# RADIO.net
KiCad netlist of a schematic drawn in Altium Designer
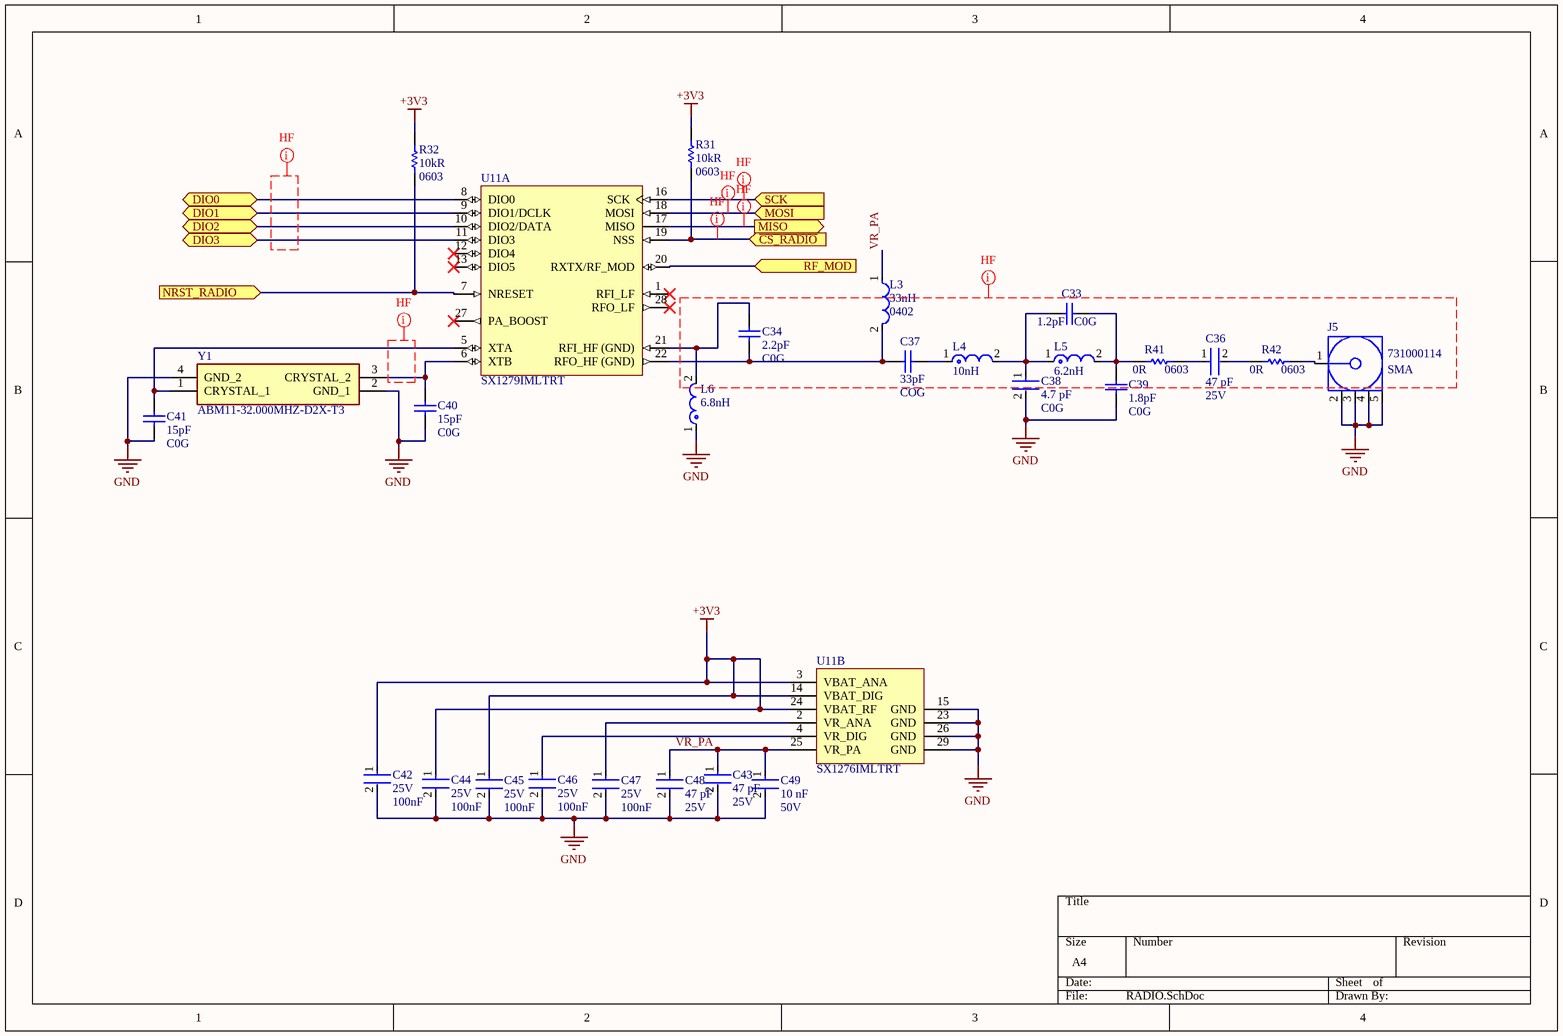
[diagram p0: RADIO.SchDoc]

(export (version "E")
  (design (tool "Eeschema 10.0.6"))
  (components
    (comp (ref "C33")
      (value "06032U1R2BAT2A")
      (footprint "CAPC1508X91X25LL25T13")
      (fields
        (field (name "MANUFACTURER") "AVX Interconnect / Elco")
        (field (name "CAPACITANCE") "1.2pF")
        (field (name "DIELECTRIC") "C0G")
        (field (name "VOLTAGE") "200V")
        (field (name "TOLERANCE") "2%")
      )
      (libsource (lib "Altium Content Vault") (part "CAP"))
    )
    (comp (ref "C34")
      (value "04023A2R2CAT2A")
      (footprint "CAPC1005X56X25ML10T15")
      (fields
        (field (name "MANUFACTURER") "AVX Interconnect / Elco")
        (field (name "CAPACITANCE") "2.2pF")
        (field (name "DIELECTRIC") "C0G")
      )
      (libsource (lib "Altium Content Vault") (part "CAP"))
    )
    (comp (ref "C36")
      (value "C0603C470J3GACTU")
      (footprint "FP-C0603C-CF-MFG")
      (description "CAP CER 47PF 25V 5% NP0 0603")
      (fields
        (field (name "CAPACITANCE") "47 pF")
        (field (name "OCTOPART") "https://octopart.com/c0603c470j3gactu-kemet-8375742")
        (field (name "MANUFACTURER") "KEMET")
        (field (name "VOLTAGE RATING (DC)") "25V")
      )
      (libsource (lib "Altium Content Vault") (part "b4654b650e69147ec39a6b967a45e02"))
    )
    (comp (ref "C37")
      (value "CC0603JRNPO9BN330")
      (footprint "CAPC1608X90X40LL10T20")
      (description "Chip Capacitor, 33 pF, +/- 5%, 50 V, -55 to 125 degC, 0603 (1608 Metric), RoHS, Tape and Reel")
      (fields
        (field (name "MANUFACTURER") "Yageo")
        (field (name "TOLERANCE") "±5%")
        (field (name "CAPACITANCE") "33pF")
        (field (name "TEMPERATURE COEFFICIENT") "COG")
      )
      (libsource (lib "Altium Content Vault") (part "CAP-NP-2"))
    )
    (comp (ref "C38")
      (value "C0603C479C5GACTU")
      (footprint "FP-C0603C-CF-MFG")
      (description "CAP CER 4.7PF 50V NP0 0603")
      (fields
        (field (name "OCTOPART") "https://octopart.com/c0603c479c5gactu-kemet-3648287")
        (field (name "TOLERANCE") "0.25 pF")
        (field (name "CAPACITANCE") "4.7 pF")
        (field (name "TEMPERATURE CHARACTERISTIC") "C0G")
      )
      (libsource (lib "Altium Content Vault") (part "b4654b650e69147ec39a6b967a45e02"))
    )
    (comp (ref "C39")
      (value "06032U1R8BAT2A")
      (footprint "CAPC1508X91X25NL25T13")
      (fields
        (field (name "MANUFACTURER") "AVX Interconnect / Elco")
        (field (name "CAPACITANCE") "1.8pF")
        (field (name "DIELECTRIC") "C0G")
        (field (name "VOLTAGE") "200V")
      )
      (libsource (lib "Altium Content Vault") (part "CAP"))
    )
    (comp (ref "C40")
      (value "VJ0603D150JXPAJ")
      (footprint "CAPC1608X92X38ML15T08")
      (fields
        (field (name "MANUFACTURER") "Vitramon")
        (field (name "TOLERANCE") "5%")
        (field (name "CAPACITANCE") "15pF")
        (field (name "DIELECTRIC") "C0G")
        (field (name "VOLTAGE") "250V")
      )
      (libsource (lib "Altium Content Vault") (part "CAP"))
    )
    (comp (ref "C41")
      (value "VJ0603D150JXPAJ")
      (footprint "CAPC1608X92X38ML15T08")
      (fields
        (field (name "MANUFACTURER") "Vitramon")
        (field (name "TOLERANCE") "5%")
        (field (name "CAPACITANCE") "15pF")
        (field (name "DIELECTRIC") "C0G")
        (field (name "VOLTAGE") "250V")
      )
      (libsource (lib "Altium Content Vault") (part "CAP"))
    )
    (comp (ref "C42")
      (value "CGA3E2X7R1E104K080AA")
      (footprint "FP-CGA3E-0_3-0_1-MFG")
      (description "Cap Ceramic 100nF 25V X7R 10% Pad SMD 0603 +125°C Automotive T/R")
      (fields
        (field (name "VOLTAGE RATING (DC)") "25V")
        (field (name "CAPACITANCE") "100nF")
        (field (name "TOLERANCE") "10%")
        (field (name "MANUFACTURER") "TDK")
      )
      (libsource (lib "Altium Content Vault") (part "b4654b650e69147ec39a6b967a45e02"))
    )
    (comp (ref "C43")
      (value "C0603C470J3GACTU")
      (footprint "FP-C0603C-CF-MFG")
      (description "CAP CER 47PF 25V 5% NP0 0603")
      (fields
        (field (name "CAPACITANCE") "47 pF")
        (field (name "OCTOPART") "https://octopart.com/c0603c470j3gactu-kemet-8375742")
        (field (name "MANUFACTURER") "KEMET")
        (field (name "VOLTAGE RATING (DC)") "25V")
      )
      (libsource (lib "Altium Content Vault") (part "b4654b650e69147ec39a6b967a45e02"))
    )
    (comp (ref "C44")
      (value "CGA3E2X7R1E104K080AA")
      (footprint "FP-CGA3E-0_3-0_1-MFG")
      (description "Cap Ceramic 100nF 25V X7R 10% Pad SMD 0603 +125°C Automotive T/R")
      (fields
        (field (name "VOLTAGE RATING (DC)") "25V")
        (field (name "CAPACITANCE") "100nF")
        (field (name "TOLERANCE") "10%")
        (field (name "MANUFACTURER") "TDK")
      )
      (libsource (lib "Altium Content Vault") (part "b4654b650e69147ec39a6b967a45e02"))
    )
    (comp (ref "C45")
      (value "CGA3E2X7R1E104K080AA")
      (footprint "FP-CGA3E-0_3-0_1-MFG")
      (description "Cap Ceramic 100nF 25V X7R 10% Pad SMD 0603 +125°C Automotive T/R")
      (fields
        (field (name "VOLTAGE RATING (DC)") "25V")
        (field (name "CAPACITANCE") "100nF")
        (field (name "TOLERANCE") "10%")
        (field (name "MANUFACTURER") "TDK")
      )
      (libsource (lib "Altium Content Vault") (part "b4654b650e69147ec39a6b967a45e02"))
    )
    (comp (ref "C46")
      (value "CGA3E2X7R1E104K080AA")
      (footprint "FP-CGA3E-0_3-0_1-MFG")
      (description "Cap Ceramic 100nF 25V X7R 10% Pad SMD 0603 +125°C Automotive T/R")
      (fields
        (field (name "VOLTAGE RATING (DC)") "25V")
        (field (name "CAPACITANCE") "100nF")
        (field (name "TOLERANCE") "10%")
        (field (name "MANUFACTURER") "TDK")
      )
      (libsource (lib "Altium Content Vault") (part "b4654b650e69147ec39a6b967a45e02"))
    )
    (comp (ref "C47")
      (value "CGA3E2X7R1E104K080AA")
      (footprint "FP-CGA3E-0_3-0_1-MFG")
      (description "Cap Ceramic 100nF 25V X7R 10% Pad SMD 0603 +125°C Automotive T/R")
      (fields
        (field (name "VOLTAGE RATING (DC)") "25V")
        (field (name "CAPACITANCE") "100nF")
        (field (name "TOLERANCE") "10%")
        (field (name "MANUFACTURER") "TDK")
      )
      (libsource (lib "Altium Content Vault") (part "b4654b650e69147ec39a6b967a45e02"))
    )
    (comp (ref "C48")
      (value "C0603C470J3GACTU")
      (footprint "FP-C0603C-CF-MFG")
      (description "CAP CER 47PF 25V 5% NP0 0603")
      (fields
        (field (name "CAPACITANCE") "47 pF")
        (field (name "OCTOPART") "https://octopart.com/c0603c470j3gactu-kemet-8375742")
        (field (name "MANUFACTURER") "KEMET")
        (field (name "VOLTAGE RATING (DC)") "25V")
      )
      (libsource (lib "Altium Content Vault") (part "b4654b650e69147ec39a6b967a45e02"))
    )
    (comp (ref "C49")
      (value "CC0603KRX7R9BB103")
      (footprint "FP-CC0603-DA-MFG")
      (description "CAP CER 10000PF 50V X7R 0603")
      (fields
        (field (name "TOLERANCE") "0.1")
        (field (name "MANUFACTURER") "YAGEO")
        (field (name "CAPACITANCE") "10 nF")
        (field (name "VOLTAGE RATING (DC)") "50V")
      )
      (libsource (lib "Altium Content Vault") (part "11868f565c42a9108669ba33697ecf6"))
    )
    (comp (ref "J5")
      (value "731000114")
      (footprint "MOLX-731000114_V")
      (description "SMA Right-Angle PCB Jack Receptacle, Brass Body, Gold Plated, 50 Ohm, 5-Pin THD, RoHS, Tray")
      (fields
        (field (name "MANUFACTURER") "Molex")
        (field (name "MANUFACTURER PART NUMBER") "73100-0114")
        (field (name "CASE/PACKAGE") "SMA")
      )
      (libsource (lib "Altium Content Vault") (part "CN-S-4F-RF5"))
    )
    (comp (ref "L3")
      (value "LQW15AN33NJ00D")
      (footprint "FP-LQW15AN_00-W0_5-0_1-MFG")
      (description "Wire Wound RF Inductor 33nH ±5% 260mA 0.63Ω 0402 (1005)")
      (fields
        (field (name "TOLERANCE") "5%")
        (field (name "INDUCTANCE") "33nH")
        (field (name "CASE/PACKAGE") "0402")
        (field (name "MANUFACTURER") "Murata")
      )
      (libsource (lib "Altium Content Vault") (part "725321dda6339637d4d059423bc1c3c"))
    )
    (comp (ref "L4")
      (value "LQG15HS10NJ02D")
      (footprint "FP-LQG15HH_02-IPC_A")
      (description "Multilayer type RF Inductor 10nH ±5% 0.26Ω 500mA 0402")
      (fields
        (field (name "INDUCTANCE") "10nH")
        (field (name "TOLERANCE") "5%")
        (field (name "MANUFACTURER") "Murata")
      )
      (libsource (lib "Altium Content Vault") (part "4cc4b267dca4c8e51f7102f422741d8"))
    )
    (comp (ref "L5")
      (value "LQG15HS6N2S02D")
      (footprint "FP-LQG15HH_02-IPC_C")
      (description "Multilayer type RF Inductor 6.2nH ±0.3nH 0.2Ω 600mA 0402")
      (fields (field (name "INDUCTANCE") "6.2nH"))
      (libsource (lib "Altium Content Vault") (part "4cc4b267dca4c8e51f7102f422741d8"))
    )
    (comp (ref "L6")
      (value "LQG15HS6N8J02D")
      (footprint "FP-LQG15HH_02-IPC_A")
      (description "Multilayer type RF Inductor 6.8nH ±5% 0.22Ω 600mA 0402")
      (fields
        (field (name "INDUCTANCE") "6.8nH")
        (field (name "TOLERANCE") "5%")
        (field (name "MANUFACTURER") "Murata")
      )
      (libsource (lib "Altium Content Vault") (part "4cc4b267dca4c8e51f7102f422741d8"))
    )
    (comp (ref "R31")
      (value "ERJ3EKF1002V")
      (footprint "RESC1609X55X30LL15T15")
      (description "Chip Resistor, 10 KOhm, +/- 1%, 0.1 W, -55 to 155 degC, 0603 (1608 Metric), RoHS, Tape and Reel")
      (fields
        (field (name "RESISTANCE") "10kR")
        (field (name "CASE CODE (IMPERIAL)") "0603")
        (field (name "TOLERANCE") "1%")
        (field (name "MANUFACTURER") "Panasonic")
      )
      (libsource (lib "Altium Content Vault") (part "RES-2"))
    )
    (comp (ref "R32")
      (value "ERJ3EKF1002V")
      (footprint "RESC1609X55X30LL15T15")
      (description "Chip Resistor, 10 KOhm, +/- 1%, 0.1 W, -55 to 155 degC, 0603 (1608 Metric), RoHS, Tape and Reel")
      (fields
        (field (name "RESISTANCE") "10kR")
        (field (name "CASE CODE (IMPERIAL)") "0603")
        (field (name "TOLERANCE") "1%")
        (field (name "MANUFACTURER") "Panasonic")
      )
      (libsource (lib "Altium Content Vault") (part "RES-2"))
    )
    (comp (ref "R41")
      (value "RC0603JR-070RL")
      (footprint "RESC1608X55X25ML10T15")
      (description "Chip Resistor, 0 Ohm, +/- 5%, 0.1 W, -55 to 155 degC, 0603 (1608 Metric), RoHS, Tape and Reel")
      (fields
        (field (name "TOLERANCE") "5%")
        (field (name "CASE CODE (IMPERIAL)") "0603")
        (field (name "RESISTANCE") "0R")
        (field (name "MANUFACTURER") "Yageo")
      )
      (libsource (lib "Altium Content Vault") (part "RES-2"))
    )
    (comp (ref "R42")
      (value "RC0603JR-070RL")
      (footprint "RESC1608X55X25ML10T15")
      (description "Chip Resistor, 0 Ohm, +/- 5%, 0.1 W, -55 to 155 degC, 0603 (1608 Metric), RoHS, Tape and Reel")
      (fields
        (field (name "TOLERANCE") "5%")
        (field (name "CASE CODE (IMPERIAL)") "0603")
        (field (name "RESISTANCE") "0R")
        (field (name "MANUFACTURER") "Yageo")
      )
      (libsource (lib "Altium Content Vault") (part "RES-2"))
    )
    (comp (ref "U11")
      (value "SX1279IMLTRT")
      (footprint "SMTC-QFN-28_V")
      (description "Low Power Long Range Transceiver, 137 to 1020 MHz, -40 to 85 degC, 28-Pin QFN, RoHS, Tape and Reel")
      (fields
        (field (name "MANUFACTURER") "Semtech")
        (field (name "MANUFACTURER PART NUMBER") "SX1276IMLTRT")
      )
      (libsource (lib "Altium Content Vault") (part "SMTC-SX127X-QFN-28"))
    )
    (comp (ref "Y1")
      (value "ABM11-32.000MHZ-D2X-T3")
      (footprint "SamacSys:ABM1132000MHZD2XT3")
      (description "Crystal or Oscillator")
      (fields (field (name "MOUSER PART NUMBER") "815-ABM11-32-D2XT3"))
      (libsource (lib "*") (part "ABM11-32.000MHZ-D2X-T3"))
    )
  )
  (nets
    (net (code "1") (name "+3V3") (class "Default")
      (node (ref "C42") (pin "1") (pinfunction "1_1") (pintype "passive"))
      (node (ref "C44") (pin "1") (pinfunction "1_1") (pintype "passive"))
      (node (ref "C45") (pin "1") (pinfunction "1_1") (pintype "passive"))
      (node (ref "R31") (pin "2") (pinfunction "2_2") (pintype "passive"))
      (node (ref "R32") (pin "2") (pinfunction "2_2") (pintype "passive"))
      (node (ref "U11") (pin "14") (pinfunction "VBAT_DIG_14") (pintype "power_in"))
      (node (ref "U11") (pin "24") (pinfunction "VBAT_RF_24") (pintype "power_in"))
      (node (ref "U11") (pin "3") (pinfunction "VBAT_ANA_3") (pintype "power_in"))
    )
    (net (code "2") (name "/CS_RADIO") (class "Default")
      (node (ref "R31") (pin "1") (pinfunction "1_1") (pintype "passive"))
      (node (ref "U11") (pin "19") (pinfunction "NSS_19") (pintype "input"))
    )
    (net (code "3") (name "/DIO0") (class "Default")
      (node (ref "U11") (pin "8") (pinfunction "DIO0_8") (pintype "bidirectional"))
    )
    (net (code "4") (name "/DIO1") (class "Default")
      (node (ref "U11") (pin "9") (pinfunction "DIO1/DCLK_9") (pintype "bidirectional"))
    )
    (net (code "5") (name "/DIO2") (class "Default")
      (node (ref "U11") (pin "10") (pinfunction "DIO2/DATA_10") (pintype "bidirectional"))
    )
    (net (code "6") (name "/DIO3") (class "Default")
      (node (ref "U11") (pin "11") (pinfunction "DIO3_11") (pintype "bidirectional"))
    )
    (net (code "7") (name "/MISO") (class "Default")
      (node (ref "U11") (pin "17") (pinfunction "MISO_17") (pintype "tri_state"))
    )
    (net (code "8") (name "/MOSI") (class "Default")
      (node (ref "U11") (pin "18") (pinfunction "MOSI_18") (pintype "input"))
    )
    (net (code "9") (name "/NRST_RADIO") (class "Default")
      (node (ref "R32") (pin "1") (pinfunction "1_1") (pintype "passive"))
      (node (ref "U11") (pin "7") (pinfunction "NRESET_7") (pintype "input"))
    )
    (net (code "10") (name "/RF_MOD") (class "Default")
      (node (ref "U11") (pin "20") (pinfunction "RXTX/RF_MOD_20") (pintype "bidirectional"))
    )
    (net (code "11") (name "/SCK") (class "Default")
      (node (ref "U11") (pin "16") (pinfunction "SCK_16") (pintype "input"))
    )
    (net (code "12") (name "/VR_PA") (class "Default")
      (node (ref "C43") (pin "1") (pinfunction "1_1") (pintype "passive"))
      (node (ref "C48") (pin "1") (pinfunction "1_1") (pintype "passive"))
      (node (ref "C49") (pin "1") (pinfunction "1_1") (pintype "passive"))
      (node (ref "L3") (pin "1") (pinfunction "1_1") (pintype "passive"))
      (node (ref "U11") (pin "25") (pinfunction "VR_PA_25") (pintype "power_in"))
    )
    (net (code "13") (name "GND") (class "Default")
      (node (ref "C38") (pin "2") (pinfunction "2_2") (pintype "passive"))
      (node (ref "C39") (pin "1") (pinfunction "1_1") (pintype "passive"))
      (node (ref "C40") (pin "1") (pinfunction "1_1") (pintype "passive"))
      (node (ref "C41") (pin "1") (pinfunction "1_1") (pintype "passive"))
      (node (ref "C42") (pin "2") (pinfunction "2_2") (pintype "passive"))
      (node (ref "C43") (pin "2") (pinfunction "2_2") (pintype "passive"))
      (node (ref "C44") (pin "2") (pinfunction "2_2") (pintype "passive"))
      (node (ref "C45") (pin "2") (pinfunction "2_2") (pintype "passive"))
      (node (ref "C46") (pin "2") (pinfunction "2_2") (pintype "passive"))
      (node (ref "C47") (pin "2") (pinfunction "2_2") (pintype "passive"))
      (node (ref "C48") (pin "2") (pinfunction "2_2") (pintype "passive"))
      (node (ref "C49") (pin "2") (pinfunction "2_2") (pintype "passive"))
      (node (ref "J5") (pin "2") (pinfunction "2_2") (pintype "passive"))
      (node (ref "J5") (pin "3") (pinfunction "3_3") (pintype "passive"))
      (node (ref "J5") (pin "4") (pinfunction "4_4") (pintype "passive"))
      (node (ref "J5") (pin "5") (pinfunction "5_5") (pintype "passive"))
      (node (ref "L6") (pin "1") (pinfunction "1_1") (pintype "passive"))
      (node (ref "U11") (pin "15") (pinfunction "GND_15") (pintype "power_in"))
      (node (ref "U11") (pin "23") (pinfunction "GND_23") (pintype "power_in"))
      (node (ref "U11") (pin "26") (pinfunction "GND_26") (pintype "power_in"))
      (node (ref "U11") (pin "29") (pinfunction "GND_29") (pintype "power_in"))
      (node (ref "Y1") (pin "2") (pinfunction "GND_1_2") (pintype "passive"))
      (node (ref "Y1") (pin "4") (pinfunction "GND_2_4") (pintype "passive"))
    )
    (net (code "14") (name "Net-(C33-Pad1)") (class "Default")
      (node (ref "C33") (pin "1") (pinfunction "1_1") (pintype "passive"))
      (node (ref "C38") (pin "1") (pinfunction "1_1") (pintype "passive"))
      (node (ref "L4") (pin "2") (pinfunction "2_2") (pintype "passive"))
      (node (ref "L5") (pin "1") (pinfunction "1_1") (pintype "passive"))
    )
    (net (code "15") (name "Net-(C33-Pad2)") (class "Default")
      (node (ref "C33") (pin "2") (pinfunction "2_2") (pintype "passive"))
      (node (ref "C39") (pin "2") (pinfunction "2_2") (pintype "passive"))
      (node (ref "L5") (pin "2") (pinfunction "2_2") (pintype "passive"))
      (node (ref "R41") (pin "1") (pinfunction "1_1") (pintype "passive"))
    )
    (net (code "16") (name "Net-(C36-Pad1)") (class "Default")
      (node (ref "C36") (pin "1") (pinfunction "1_1") (pintype "passive"))
      (node (ref "R41") (pin "2") (pinfunction "2_2") (pintype "passive"))
    )
    (net (code "17") (name "Net-(C36-Pad2)") (class "Default")
      (node (ref "C36") (pin "2") (pinfunction "2_2") (pintype "passive"))
      (node (ref "R42") (pin "1") (pinfunction "1_1") (pintype "passive"))
    )
    (net (code "18") (name "Net-(C37-Pad1)") (class "Default")
      (node (ref "C37") (pin "1") (pinfunction "1_1") (pintype "passive"))
      (node (ref "L4") (pin "1") (pinfunction "1_1") (pintype "passive"))
    )
    (net (code "19") (name "Net-(J5-Pad1)") (class "Default")
      (node (ref "J5") (pin "1") (pinfunction "1_1") (pintype "passive"))
      (node (ref "R42") (pin "2") (pinfunction "2_2") (pintype "passive"))
    )
    (net (code "20") (name "Net-(U11A-RFI_HF_(GND))") (class "Default")
      (node (ref "C34") (pin "1") (pinfunction "1_1") (pintype "passive"))
      (node (ref "L6") (pin "2") (pinfunction "2_2") (pintype "passive"))
      (node (ref "U11") (pin "21") (pinfunction "RFI_HF_(GND)_21") (pintype "input"))
    )
    (net (code "21") (name "Net-(U11A-RFO_HF_(GND))") (class "Default")
      (node (ref "C34") (pin "2") (pinfunction "2_2") (pintype "passive"))
      (node (ref "C37") (pin "2") (pinfunction "2_2") (pintype "passive"))
      (node (ref "L3") (pin "2") (pinfunction "2_2") (pintype "passive"))
      (node (ref "U11") (pin "22") (pinfunction "RFO_HF_(GND)_22") (pintype "output"))
    )
    (net (code "22") (name "Net-(U11A-XTA)") (class "Default")
      (node (ref "C41") (pin "2") (pinfunction "2_2") (pintype "passive"))
      (node (ref "U11") (pin "5") (pinfunction "XTA_5") (pintype "bidirectional"))
      (node (ref "Y1") (pin "1") (pinfunction "CRYSTAL_1_1") (pintype "passive"))
    )
    (net (code "23") (name "Net-(U11A-XTB)") (class "Default")
      (node (ref "C40") (pin "2") (pinfunction "2_2") (pintype "passive"))
      (node (ref "U11") (pin "6") (pinfunction "XTB_6") (pintype "bidirectional"))
      (node (ref "Y1") (pin "3") (pinfunction "CRYSTAL_2_3") (pintype "passive"))
    )
    (net (code "24") (name "Net-(U11B-VR_ANA)") (class "Default")
      (node (ref "C47") (pin "1") (pinfunction "1_1") (pintype "passive"))
      (node (ref "U11") (pin "2") (pinfunction "VR_ANA_2") (pintype "power_in"))
    )
    (net (code "25") (name "Net-(U11B-VR_DIG)") (class "Default")
      (node (ref "C46") (pin "1") (pinfunction "1_1") (pintype "passive"))
      (node (ref "U11") (pin "4") (pinfunction "VR_DIG_4") (pintype "power_in"))
    )
    (net (code "26") (name "unconnected-(U11A-DIO4-Pad12)") (class "Default")
      (node (ref "U11") (pin "12") (pinfunction "DIO4_12") (pintype "bidirectional+no_connect"))
    )
    (net (code "27") (name "unconnected-(U11A-DIO5-Pad13)") (class "Default")
      (node (ref "U11") (pin "13") (pinfunction "DIO5_13") (pintype "bidirectional+no_connect"))
    )
    (net (code "28") (name "unconnected-(U11A-PA_BOOST-Pad27)") (class "Default")
      (node (ref "U11") (pin "27") (pinfunction "PA_BOOST_27") (pintype "output+no_connect"))
    )
    (net (code "29") (name "unconnected-(U11A-RFI_LF-Pad1)") (class "Default")
      (node (ref "U11") (pin "1") (pinfunction "RFI_LF_1") (pintype "input+no_connect"))
    )
    (net (code "30") (name "unconnected-(U11A-RFO_LF-Pad28)") (class "Default")
      (node (ref "U11") (pin "28") (pinfunction "RFO_LF_28") (pintype "output+no_connect"))
    )
  )
)
